# Steering_Wheel_USB.net
KiCad netlist of a schematic drawn in EAGLE
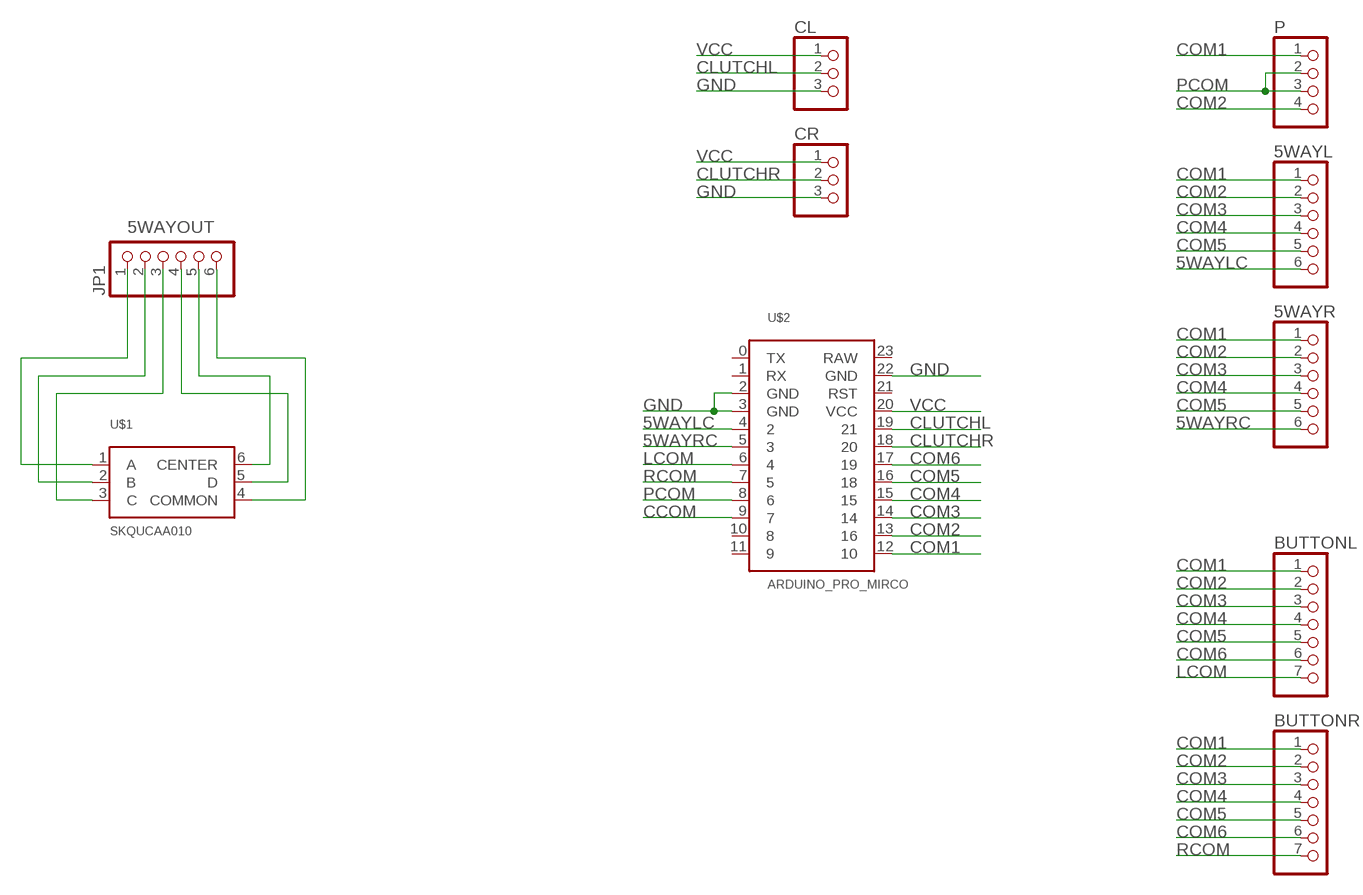
[diagram p0: schematic, sheet 1]

(export (version "E")
  (design (tool "Eeschema 10.0.6"))
  (components
    (comp (ref "5WAYL")
      (value "PINHD-1X6")
      (footprint "eagle-import:1X06")
      (libsource (lib "eagle-import") (part "PINHD-1X6"))
    )
    (comp (ref "5WAYR")
      (value "PINHD-1X6")
      (footprint "eagle-import:1X06")
      (libsource (lib "eagle-import") (part "PINHD-1X6"))
    )
    (comp (ref "BUTTONL")
      (value "PINHD-1X7")
      (footprint "eagle-import:1X07")
      (libsource (lib "eagle-import") (part "PINHD-1X7"))
    )
    (comp (ref "BUTTONR")
      (value "PINHD-1X7")
      (footprint "eagle-import:1X07")
      (libsource (lib "eagle-import") (part "PINHD-1X7"))
    )
    (comp (ref "CL")
      (value "PINHD-1X3")
      (footprint "eagle-import:1X03")
      (libsource (lib "eagle-import") (part "PINHD-1X3"))
    )
    (comp (ref "CR")
      (value "PINHD-1X3")
      (footprint "eagle-import:1X03")
      (libsource (lib "eagle-import") (part "PINHD-1X3"))
    )
    (comp (ref "JP1")
      (value "PINHD-1X6")
      (footprint "eagle-import:1X06")
      (libsource (lib "eagle-import") (part "PINHD-1X6"))
    )
    (comp (ref "P")
      (value "PINHD-1X4")
      (footprint "eagle-import:1X04")
      (libsource (lib "eagle-import") (part "PINHD-1X4"))
    )
    (comp (ref "U$1")
      (value "SKQUCAA010")
      (footprint "eagle-import:SKQUCAA010")
      (libsource (lib "eagle-import") (part "SKQUCAA010"))
    )
    (comp (ref "U$2")
      (value "ARDUINO_PRO_MIRCO")
      (footprint "eagle-import:ARDUINO_PRO_MICRO")
      (libsource (lib "eagle-import") (part "ARDUINO_PRO_MIRCO"))
    )
  )
  (nets
    (net (code "1") (name "/5WAYLC") (class "Default")
      (node (ref "5WAYL") (pin "6") (pinfunction "6_6") (pintype "passive"))
      (node (ref "U$2") (pin "4") (pinfunction "2_4") (pintype "bidirectional"))
    )
    (net (code "2") (name "/5WAYOUT") (class "Default")
      (node (ref "JP1") (pin "1") (pinfunction "1_1") (pintype "passive"))
      (node (ref "U$1") (pin "1") (pinfunction "A_1") (pintype "bidirectional"))
    )
    (net (code "3") (name "/5WAYRC") (class "Default")
      (node (ref "5WAYR") (pin "6") (pinfunction "6_6") (pintype "passive"))
      (node (ref "U$2") (pin "5") (pinfunction "3_5") (pintype "bidirectional"))
    )
    (net (code "4") (name "/CCOM") (class "Default")
      (node (ref "U$2") (pin "9") (pinfunction "7_9") (pintype "bidirectional"))
    )
    (net (code "5") (name "/CLUTCHL") (class "Default")
      (node (ref "CL") (pin "2") (pinfunction "2_2") (pintype "passive"))
      (node (ref "U$2") (pin "19") (pinfunction "21_19") (pintype "bidirectional"))
    )
    (net (code "6") (name "/CLUTCHR") (class "Default")
      (node (ref "CR") (pin "2") (pinfunction "2_2") (pintype "passive"))
      (node (ref "U$2") (pin "18") (pinfunction "20_18") (pintype "bidirectional"))
    )
    (net (code "7") (name "/COM1") (class "Default")
      (node (ref "5WAYL") (pin "1") (pinfunction "1_1") (pintype "passive"))
      (node (ref "5WAYR") (pin "1") (pinfunction "1_1") (pintype "passive"))
      (node (ref "BUTTONL") (pin "1") (pinfunction "1_1") (pintype "passive"))
      (node (ref "BUTTONR") (pin "1") (pinfunction "1_1") (pintype "passive"))
      (node (ref "P") (pin "1") (pinfunction "1_1") (pintype "passive"))
      (node (ref "U$2") (pin "12") (pinfunction "10_12") (pintype "bidirectional"))
    )
    (net (code "8") (name "/COM2") (class "Default")
      (node (ref "5WAYL") (pin "2") (pinfunction "2_2") (pintype "passive"))
      (node (ref "5WAYR") (pin "2") (pinfunction "2_2") (pintype "passive"))
      (node (ref "BUTTONL") (pin "2") (pinfunction "2_2") (pintype "passive"))
      (node (ref "BUTTONR") (pin "2") (pinfunction "2_2") (pintype "passive"))
      (node (ref "P") (pin "4") (pinfunction "4_4") (pintype "passive"))
      (node (ref "U$2") (pin "13") (pinfunction "16_13") (pintype "bidirectional"))
    )
    (net (code "9") (name "/COM3") (class "Default")
      (node (ref "5WAYL") (pin "3") (pinfunction "3_3") (pintype "passive"))
      (node (ref "5WAYR") (pin "3") (pinfunction "3_3") (pintype "passive"))
      (node (ref "BUTTONL") (pin "3") (pinfunction "3_3") (pintype "passive"))
      (node (ref "BUTTONR") (pin "3") (pinfunction "3_3") (pintype "passive"))
      (node (ref "U$2") (pin "14") (pinfunction "14_14") (pintype "bidirectional"))
    )
    (net (code "10") (name "/COM4") (class "Default")
      (node (ref "5WAYL") (pin "4") (pinfunction "4_4") (pintype "passive"))
      (node (ref "5WAYR") (pin "4") (pinfunction "4_4") (pintype "passive"))
      (node (ref "BUTTONL") (pin "4") (pinfunction "4_4") (pintype "passive"))
      (node (ref "BUTTONR") (pin "4") (pinfunction "4_4") (pintype "passive"))
      (node (ref "U$2") (pin "15") (pinfunction "15_15") (pintype "bidirectional"))
    )
    (net (code "11") (name "/COM5") (class "Default")
      (node (ref "5WAYL") (pin "5") (pinfunction "5_5") (pintype "passive"))
      (node (ref "5WAYR") (pin "5") (pinfunction "5_5") (pintype "passive"))
      (node (ref "BUTTONL") (pin "5") (pinfunction "5_5") (pintype "passive"))
      (node (ref "BUTTONR") (pin "5") (pinfunction "5_5") (pintype "passive"))
      (node (ref "U$2") (pin "16") (pinfunction "18_16") (pintype "bidirectional"))
    )
    (net (code "12") (name "/COM6") (class "Default")
      (node (ref "BUTTONL") (pin "6") (pinfunction "6_6") (pintype "passive"))
      (node (ref "BUTTONR") (pin "6") (pinfunction "6_6") (pintype "passive"))
      (node (ref "U$2") (pin "17") (pinfunction "19_17") (pintype "bidirectional"))
    )
    (net (code "13") (name "/GND") (class "Default")
      (node (ref "CL") (pin "3") (pinfunction "3_3") (pintype "passive"))
      (node (ref "CR") (pin "3") (pinfunction "3_3") (pintype "passive"))
      (node (ref "U$2") (pin "2") (pinfunction "GND_2") (pintype "bidirectional"))
      (node (ref "U$2") (pin "22") (pinfunction "GND_22") (pintype "bidirectional"))
      (node (ref "U$2") (pin "3") (pinfunction "GND_3") (pintype "bidirectional"))
    )
    (net (code "14") (name "/LCOM") (class "Default")
      (node (ref "BUTTONL") (pin "7") (pinfunction "7_7") (pintype "passive"))
      (node (ref "U$2") (pin "6") (pinfunction "4_6") (pintype "bidirectional"))
    )
    (net (code "15") (name "/PCOM") (class "Default")
      (node (ref "P") (pin "2") (pinfunction "2_2") (pintype "passive"))
      (node (ref "P") (pin "3") (pinfunction "3_3") (pintype "passive"))
      (node (ref "U$2") (pin "8") (pinfunction "6_8") (pintype "bidirectional"))
    )
    (net (code "16") (name "/RCOM") (class "Default")
      (node (ref "BUTTONR") (pin "7") (pinfunction "7_7") (pintype "passive"))
      (node (ref "U$2") (pin "7") (pinfunction "5_7") (pintype "bidirectional"))
    )
    (net (code "17") (name "/VCC") (class "Default")
      (node (ref "CL") (pin "1") (pinfunction "1_1") (pintype "passive"))
      (node (ref "CR") (pin "1") (pinfunction "1_1") (pintype "passive"))
      (node (ref "U$2") (pin "20") (pinfunction "VCC_20") (pintype "bidirectional"))
    )
    (net (code "18") (name "Net-(U$1-B)") (class "Default")
      (node (ref "JP1") (pin "2") (pinfunction "2_2") (pintype "passive"))
      (node (ref "U$1") (pin "2") (pinfunction "B_2") (pintype "bidirectional"))
    )
    (net (code "19") (name "Net-(U$1-C)") (class "Default")
      (node (ref "JP1") (pin "3") (pinfunction "3_3") (pintype "passive"))
      (node (ref "U$1") (pin "3") (pinfunction "C_3") (pintype "bidirectional"))
    )
    (net (code "20") (name "Net-(U$1-CENTER)") (class "Default")
      (node (ref "JP1") (pin "5") (pinfunction "5_5") (pintype "passive"))
      (node (ref "U$1") (pin "6") (pinfunction "CENTER_6") (pintype "bidirectional"))
    )
    (net (code "21") (name "Net-(U$1-COMMON)") (class "Default")
      (node (ref "JP1") (pin "6") (pinfunction "6_6") (pintype "passive"))
      (node (ref "U$1") (pin "4") (pinfunction "COMMON_4") (pintype "bidirectional"))
    )
    (net (code "22") (name "Net-(U$1-D)") (class "Default")
      (node (ref "JP1") (pin "4") (pinfunction "4_4") (pintype "passive"))
      (node (ref "U$1") (pin "5") (pinfunction "D_5") (pintype "bidirectional"))
    )
    (net (code "23") (name "unconnected-(U$2-8-Pad10)") (class "Default")
      (node (ref "U$2") (pin "10") (pinfunction "8_10") (pintype "bidirectional"))
    )
    (net (code "24") (name "unconnected-(U$2-9-Pad11)") (class "Default")
      (node (ref "U$2") (pin "11") (pinfunction "9_11") (pintype "bidirectional"))
    )
    (net (code "25") (name "unconnected-(U$2-RAW-Pad23)") (class "Default")
      (node (ref "U$2") (pin "23") (pinfunction "RAW_23") (pintype "bidirectional"))
    )
    (net (code "26") (name "unconnected-(U$2-RST-Pad21)") (class "Default")
      (node (ref "U$2") (pin "21") (pinfunction "RST_21") (pintype "bidirectional"))
    )
    (net (code "27") (name "unconnected-(U$2-RX-Pad1)") (class "Default")
      (node (ref "U$2") (pin "1") (pinfunction "RX_1") (pintype "bidirectional"))
    )
    (net (code "28") (name "unconnected-(U$2-TX-Pad0)") (class "Default")
      (node (ref "U$2") (pin "0") (pinfunction "TX_0") (pintype "bidirectional"))
    )
  )
)
